# BrannOvergang.net
KiCad netlist of a schematic drawn in EAGLE
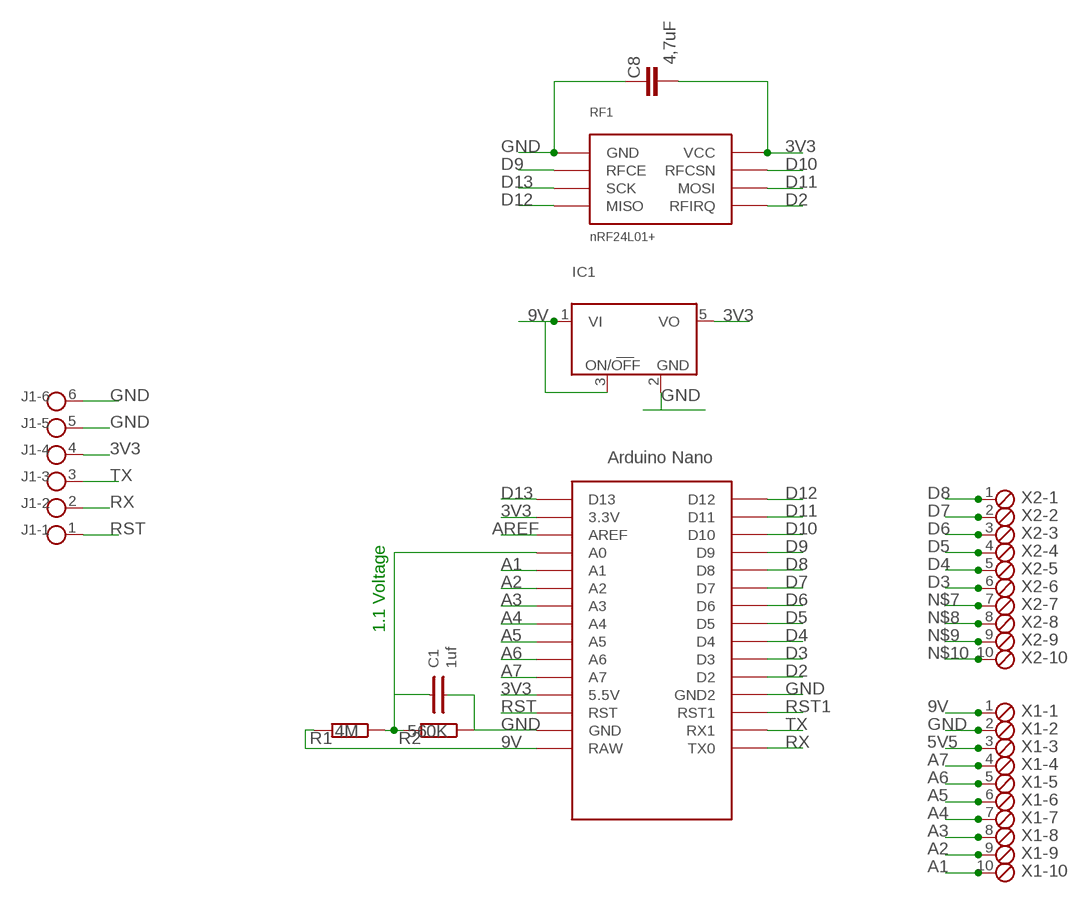
[diagram p0: schematic, sheet 1]

(export (version "E")
  (design (tool "Eeschema 10.0.6"))
  (components
    (comp (ref "C1")
      (value "1uf")
      (footprint "eagle-import:0805")
      (libsource (lib "eagle-import") (part "CC0805"))
    )
    (comp (ref "C8")
      (value "4,7uF")
      (footprint "eagle-import:C1206K")
      (libsource (lib "eagle-import") (part "C-EUC1206K"))
    )
    (comp (ref "IC1")
      (value "LP2980IM5")
      (footprint "eagle-import:SOT23-5")
      (libsource (lib "eagle-import") (part "LP2980IM5"))
    )
    (comp (ref "J1")
      (value "FTDI")
      (footprint "eagle-import:LIST6B")
      (libsource (lib "eagle-import") (part "LIST6LIST6B"))
    )
    (comp (ref "R1")
      (value "4M")
      (footprint "eagle-import:R0805")
      (libsource (lib "eagle-import") (part "R-EU_R0805"))
    )
    (comp (ref "R2")
      (value "560K")
      (footprint "eagle-import:R0805")
      (libsource (lib "eagle-import") (part "R-EU_R0805"))
    )
    (comp (ref "RF1")
      (value "nRF24L01+")
      (footprint "eagle-import:2X4-2.54MM")
      (libsource (lib "eagle-import") (part "NRF24L01"))
    )
    (comp (ref "U$1")
      (value "NANO")
      (footprint "eagle-import:NANO")
      (libsource (lib "eagle-import") (part "NANO"))
    )
    (comp (ref "X1")
      (value "MPT10")
      (footprint "eagle-import:10POL254")
      (libsource (lib "eagle-import") (part "MPT10"))
    )
    (comp (ref "X2")
      (value "MPT10")
      (footprint "eagle-import:10POL254")
      (libsource (lib "eagle-import") (part "MPT10"))
    )
  )
  (nets
    (net (code "1") (name "/3V3") (class "Default")
      (node (ref "C8") (pin "1") (pinfunction "1_1") (pintype "passive"))
      (node (ref "IC1") (pin "5") (pinfunction "VO_5") (pintype "output"))
      (node (ref "J1") (pin "4") (pinfunction "1_4") (pintype "passive"))
      (node (ref "RF1") (pin "P$2") (pinfunction "VCC_P$2") (pintype "power_in"))
      (node (ref "U$1") (pin "3.3V") (pinfunction "3.3V_3.3V") (pintype "bidirectional"))
      (node (ref "U$1") (pin "5V") (pinfunction "5.5V_5V") (pintype "bidirectional"))
    )
    (net (code "2") (name "/5V5") (class "Default")
      (node (ref "X1") (pin "3") (pinfunction "1_3") (pintype "passive"))
    )
    (net (code "3") (name "/9V") (class "Default")
      (node (ref "IC1") (pin "1") (pinfunction "VI_1") (pintype "input"))
      (node (ref "IC1") (pin "3") (pinfunction "ON/OFF_3") (pintype "input"))
      (node (ref "R1") (pin "2") (pinfunction "2_2") (pintype "passive"))
      (node (ref "U$1") (pin "RAW") (pinfunction "RAW_RAW") (pintype "bidirectional"))
      (node (ref "X1") (pin "1") (pinfunction "1_1") (pintype "passive"))
    )
    (net (code "4") (name "/A1") (class "Default")
      (node (ref "U$1") (pin "A1") (pinfunction "A1_A1") (pintype "bidirectional"))
      (node (ref "X1") (pin "10") (pinfunction "1_10") (pintype "passive"))
    )
    (net (code "5") (name "/A2") (class "Default")
      (node (ref "U$1") (pin "A2") (pinfunction "A2_A2") (pintype "bidirectional"))
      (node (ref "X1") (pin "9") (pinfunction "1_9") (pintype "passive"))
    )
    (net (code "6") (name "/A3") (class "Default")
      (node (ref "U$1") (pin "A3") (pinfunction "A3_A3") (pintype "bidirectional"))
      (node (ref "X1") (pin "8") (pinfunction "1_8") (pintype "passive"))
    )
    (net (code "7") (name "/A4") (class "Default")
      (node (ref "U$1") (pin "A4") (pinfunction "A4_A4") (pintype "bidirectional"))
      (node (ref "X1") (pin "7") (pinfunction "1_7") (pintype "passive"))
    )
    (net (code "8") (name "/A5") (class "Default")
      (node (ref "U$1") (pin "A5") (pinfunction "A5_A5") (pintype "bidirectional"))
      (node (ref "X1") (pin "6") (pinfunction "1_6") (pintype "passive"))
    )
    (net (code "9") (name "/A6") (class "Default")
      (node (ref "U$1") (pin "A6") (pinfunction "A6_A6") (pintype "bidirectional"))
      (node (ref "X1") (pin "5") (pinfunction "1_5") (pintype "passive"))
    )
    (net (code "10") (name "/A7") (class "Default")
      (node (ref "U$1") (pin "A7") (pinfunction "A7_A7") (pintype "bidirectional"))
      (node (ref "X1") (pin "4") (pinfunction "1_4") (pintype "passive"))
    )
    (net (code "11") (name "/AREF") (class "Default")
      (node (ref "U$1") (pin "AREF") (pinfunction "AREF_AREF") (pintype "bidirectional"))
    )
    (net (code "12") (name "/D2") (class "Default")
      (node (ref "RF1") (pin "P$8") (pinfunction "RFIRQ_P$8") (pintype "output"))
      (node (ref "U$1") (pin "D2") (pinfunction "D2_D2") (pintype "bidirectional"))
    )
    (net (code "13") (name "/D3") (class "Default")
      (node (ref "U$1") (pin "D3") (pinfunction "D3_D3") (pintype "bidirectional"))
      (node (ref "X2") (pin "6") (pinfunction "1_6") (pintype "passive"))
    )
    (net (code "14") (name "/D4") (class "Default")
      (node (ref "U$1") (pin "D4") (pinfunction "D4_D4") (pintype "bidirectional"))
      (node (ref "X2") (pin "5") (pinfunction "1_5") (pintype "passive"))
    )
    (net (code "15") (name "/D5") (class "Default")
      (node (ref "U$1") (pin "D5") (pinfunction "D5_D5") (pintype "bidirectional"))
      (node (ref "X2") (pin "4") (pinfunction "1_4") (pintype "passive"))
    )
    (net (code "16") (name "/D6") (class "Default")
      (node (ref "U$1") (pin "D6") (pinfunction "D6_D6") (pintype "bidirectional"))
      (node (ref "X2") (pin "3") (pinfunction "1_3") (pintype "passive"))
    )
    (net (code "17") (name "/D7") (class "Default")
      (node (ref "U$1") (pin "D7") (pinfunction "D7_D7") (pintype "bidirectional"))
      (node (ref "X2") (pin "2") (pinfunction "1_2") (pintype "passive"))
    )
    (net (code "18") (name "/D8") (class "Default")
      (node (ref "U$1") (pin "D8") (pinfunction "D8_D8") (pintype "bidirectional"))
      (node (ref "X2") (pin "1") (pinfunction "1_1") (pintype "passive"))
    )
    (net (code "19") (name "/D9") (class "Default")
      (node (ref "RF1") (pin "P$3") (pinfunction "RFCE_P$3") (pintype "input"))
      (node (ref "U$1") (pin "D9") (pinfunction "D9_D9") (pintype "bidirectional"))
    )
    (net (code "20") (name "/D10") (class "Default")
      (node (ref "RF1") (pin "P$4") (pinfunction "RFCSN_P$4") (pintype "bidirectional"))
      (node (ref "U$1") (pin "D10") (pinfunction "D10_D10") (pintype "bidirectional"))
    )
    (net (code "21") (name "/D11") (class "Default")
      (node (ref "RF1") (pin "P$6") (pinfunction "MOSI_P$6") (pintype "bidirectional"))
      (node (ref "U$1") (pin "D11") (pinfunction "D11_D11") (pintype "bidirectional"))
    )
    (net (code "22") (name "/D12") (class "Default")
      (node (ref "RF1") (pin "P$7") (pinfunction "MISO_P$7") (pintype "bidirectional"))
      (node (ref "U$1") (pin "D12") (pinfunction "D12_D12") (pintype "bidirectional"))
    )
    (net (code "23") (name "/D13") (class "Default")
      (node (ref "RF1") (pin "P$5") (pinfunction "SCK_P$5") (pintype "input"))
      (node (ref "U$1") (pin "D13") (pinfunction "D13_D13") (pintype "bidirectional"))
    )
    (net (code "24") (name "/GND") (class "Default")
      (node (ref "C1") (pin "2") (pinfunction "2_2") (pintype "passive"))
      (node (ref "C8") (pin "2") (pinfunction "2_2") (pintype "passive"))
      (node (ref "IC1") (pin "2") (pinfunction "GND_2") (pintype "power_in"))
      (node (ref "J1") (pin "5") (pinfunction "1_5") (pintype "passive"))
      (node (ref "J1") (pin "6") (pinfunction "1_6") (pintype "passive"))
      (node (ref "R2") (pin "1") (pinfunction "1_1") (pintype "passive"))
      (node (ref "RF1") (pin "P$1") (pinfunction "GND_P$1") (pintype "power_in"))
      (node (ref "U$1") (pin "GND") (pinfunction "GND_GND") (pintype "bidirectional"))
      (node (ref "U$1") (pin "GND1") (pinfunction "GND2_GND1") (pintype "bidirectional"))
      (node (ref "X1") (pin "2") (pinfunction "1_2") (pintype "passive"))
    )
    (net (code "25") (name "/N$7") (class "Default")
      (node (ref "X2") (pin "7") (pinfunction "1_7") (pintype "passive"))
    )
    (net (code "26") (name "/N$8") (class "Default")
      (node (ref "X2") (pin "8") (pinfunction "1_8") (pintype "passive"))
    )
    (net (code "27") (name "/N$9") (class "Default")
      (node (ref "X2") (pin "9") (pinfunction "1_9") (pintype "passive"))
    )
    (net (code "28") (name "/N$10") (class "Default")
      (node (ref "X2") (pin "10") (pinfunction "1_10") (pintype "passive"))
    )
    (net (code "29") (name "/RST") (class "Default")
      (node (ref "J1") (pin "1") (pinfunction "1_1") (pintype "passive"))
      (node (ref "U$1") (pin "RST") (pinfunction "RST_RST") (pintype "bidirectional"))
    )
    (net (code "30") (name "/RST1") (class "Default")
      (node (ref "U$1") (pin "RST1") (pinfunction "RST1_RST1") (pintype "bidirectional"))
    )
    (net (code "31") (name "/RX") (class "Default")
      (node (ref "J1") (pin "2") (pinfunction "1_2") (pintype "passive"))
      (node (ref "U$1") (pin "TX0") (pinfunction "TX0_TX0") (pintype "bidirectional"))
    )
    (net (code "32") (name "/TX") (class "Default")
      (node (ref "J1") (pin "3") (pinfunction "1_3") (pintype "passive"))
      (node (ref "U$1") (pin "RX1") (pinfunction "RX1_RX1") (pintype "bidirectional"))
    )
    (net (code "33") (name "Net-(C1-Pad1)") (class "Default")
      (node (ref "C1") (pin "1") (pinfunction "1_1") (pintype "passive"))
      (node (ref "R1") (pin "1") (pinfunction "1_1") (pintype "passive"))
      (node (ref "R2") (pin "2") (pinfunction "2_2") (pintype "passive"))
      (node (ref "U$1") (pin "A0") (pinfunction "A0_A0") (pintype "bidirectional"))
    )
    (net (code "34") (name "unconnected-(U$1-PadICSP1)") (class "Default")
      (node (ref "U$1") (pin "ICSP1") (pinfunction "ICSP1_ICSP1") (pintype "bidirectional"))
    )
    (net (code "35") (name "unconnected-(U$1-PadICSP2)") (class "Default")
      (node (ref "U$1") (pin "ICSP2") (pinfunction "ICSP2_ICSP2") (pintype "bidirectional"))
    )
    (net (code "36") (name "unconnected-(U$1-PadICSP3)") (class "Default")
      (node (ref "U$1") (pin "ICSP3") (pinfunction "ICSP3_ICSP3") (pintype "bidirectional"))
    )
    (net (code "37") (name "unconnected-(U$1-PadICSP4)") (class "Default")
      (node (ref "U$1") (pin "ICSP4") (pinfunction "ICSP4_ICSP4") (pintype "bidirectional"))
    )
    (net (code "38") (name "unconnected-(U$1-PadICSP5)") (class "Default")
      (node (ref "U$1") (pin "ICSP5") (pinfunction "ICSP5_ICSP5") (pintype "bidirectional"))
    )
    (net (code "39") (name "unconnected-(U$1-PadICSP6)") (class "Default")
      (node (ref "U$1") (pin "ICSP6") (pinfunction "ICSP6_ICSP6") (pintype "bidirectional"))
    )
  )
)
